# fancoil.net
KiCad netlist of a schematic drawn in EAGLE
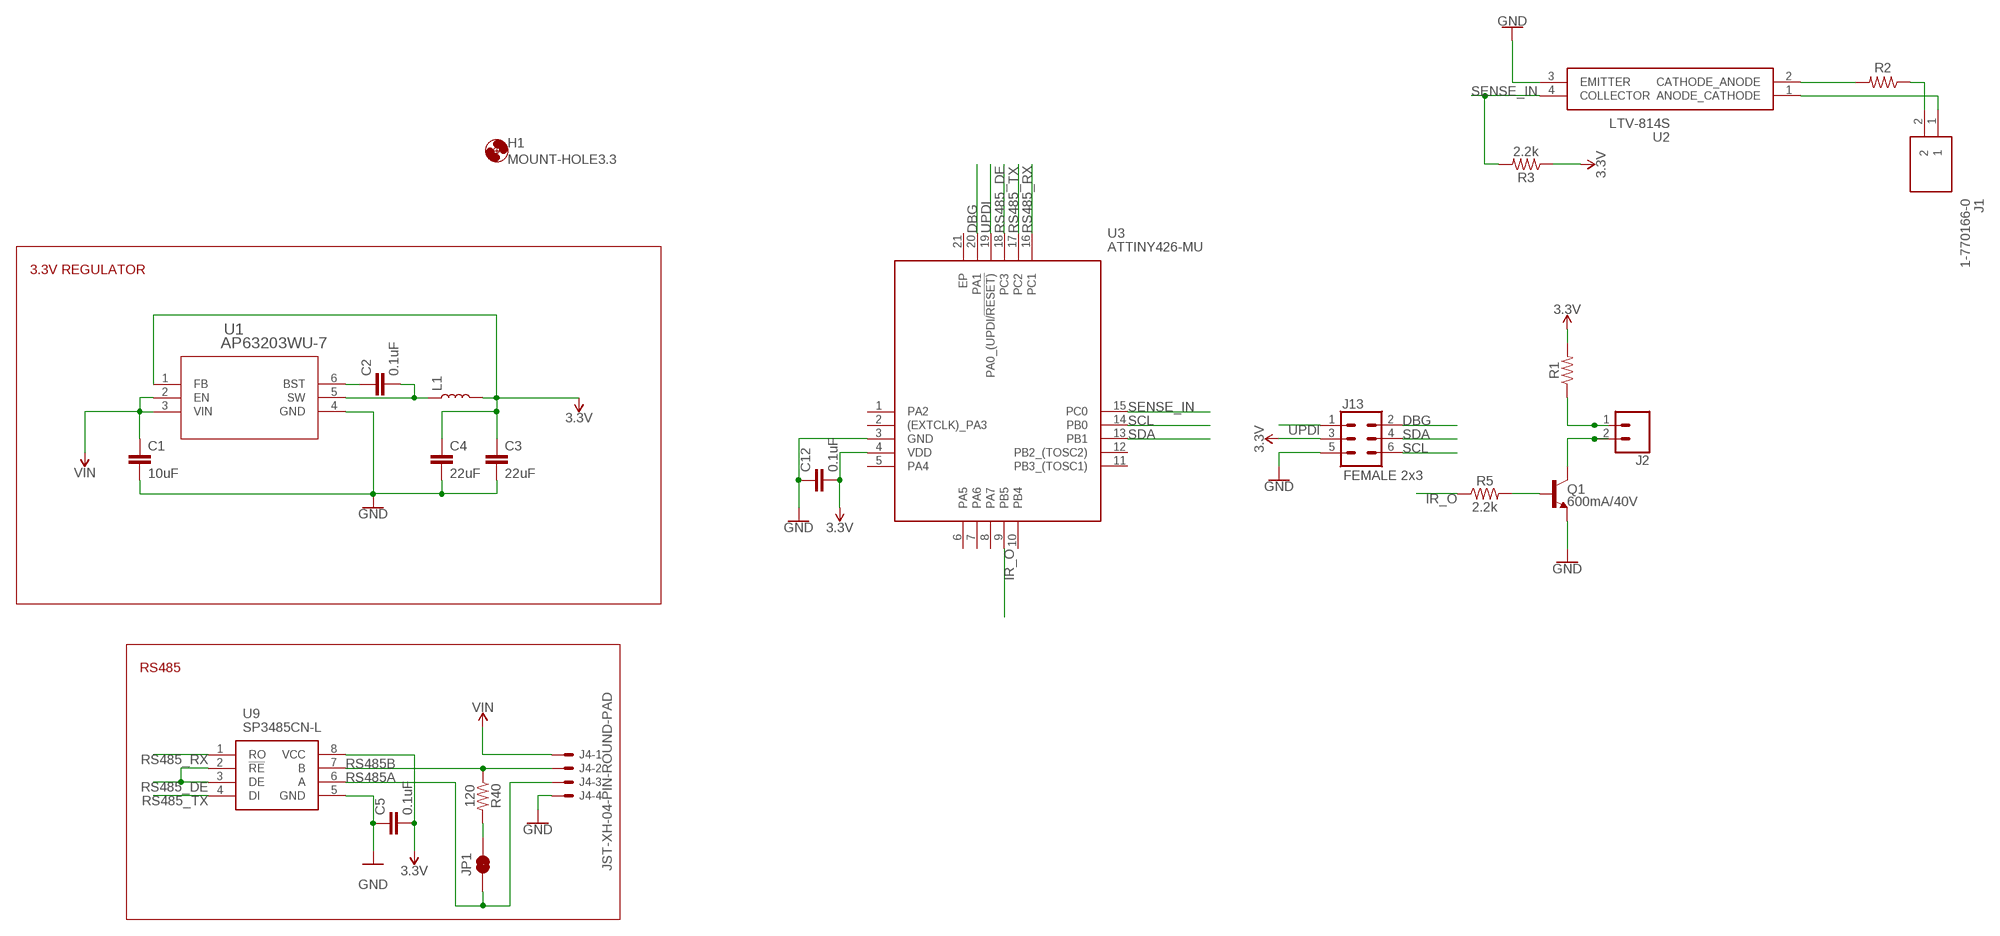
[diagram p0: schematic, sheet 1]

(export (version "E")
  (design (tool "Eeschema 10.0.6"))
  (components
    (comp (ref "C1")
      (value "10uF")
      (footprint "eagle-import:1206")
      (libsource (lib "eagle-import") (part "10UF-1206-6.3V-20%"))
    )
    (comp (ref "C2")
      (value "0.1uF")
      (footprint "eagle-import:0603")
      (libsource (lib "eagle-import") (part "0.1UF-0603-25V-5%"))
    )
    (comp (ref "C3")
      (value "22uF")
      (footprint "eagle-import:0805")
      (libsource (lib "eagle-import") (part "22UF-0805-6.3V-20%"))
    )
    (comp (ref "C4")
      (value "22uF")
      (footprint "eagle-import:0805")
      (libsource (lib "eagle-import") (part "22UF-0805-6.3V-20%"))
    )
    (comp (ref "C5")
      (value "0.1uF")
      (footprint "eagle-import:0603")
      (libsource (lib "eagle-import") (part "0.1UF-0603-25V-5%"))
    )
    (comp (ref "C12")
      (value "0.1uF")
      (footprint "eagle-import:0603")
      (libsource (lib "eagle-import") (part "0.1UF-0603-25V-5%"))
    )
    (comp (ref "H1")
      (value "MOUNT-HOLE3.3")
      (footprint "eagle-import:3,3")
      (libsource (lib "eagle-import") (part "MOUNT-HOLE3.3"))
    )
    (comp (ref "J1")
      (value "1-770166-0")
      (footprint "eagle-import:17701660")
      (fields (field (name "MOUSER_PART_NUMBER") "571-1-770166-0"))
      (libsource (lib "eagle-import") (part "1-770166-0"))
    )
    (comp (ref "J2")
      (value "CONN_02")
      (footprint "eagle-import:1X02")
      (libsource (lib "eagle-import") (part "CONN_02"))
    )
    (comp (ref "J4")
      (value "JST-XH-04-PIN-ROUND-PAD")
      (footprint "eagle-import:JST-XH-04-PACKAGE-ROUND-PAD")
      (libsource (lib "eagle-import") (part "JST-XH-04-PIN-ROUND-PAD"))
    )
    (comp (ref "J13")
      (value "FEMALE 2x3")
      (footprint "eagle-import:2X3")
      (libsource (lib "eagle-import") (part "CONN_03X2FEMALE"))
    )
    (comp (ref "JP1")
      (value "JUMPER-SMT_2_NC_TRACE_NO-SILK")
      (footprint "eagle-import:SMT-JUMPER_2_NC_TRACE_NO-SILK")
      (libsource (lib "eagle-import") (part "JUMPER-SMT_2_NC_TRACE_NO-SILK"))
    )
    (comp (ref "L1")
      (value "4.7μH_SHIELDED_INDUCTOR")
      (footprint "eagle-import:1008(2520)")
      (libsource (lib "eagle-import") (part "4.7μH_SHIELDED_INDUCTOR"))
    )
    (comp (ref "Q1")
      (value "600mA/40V")
      (footprint "eagle-import:SOT23-3")
      (libsource (lib "eagle-import") (part "TRANS_NPN-MMBT2222AL"))
    )
    (comp (ref "R1")
      (value "68OHM-0603-1/10W-1%")
      (footprint "eagle-import:0603")
      (libsource (lib "eagle-import") (part "68OHM-0603-1/10W-1%"))
    )
    (comp (ref "R2")
      (value "RESISTORAXIAL-0.3")
      (footprint "eagle-import:AXIAL-0.3")
      (libsource (lib "eagle-import") (part "RESISTORAXIAL-0.3"))
    )
    (comp (ref "R3")
      (value "2.2k")
      (footprint "eagle-import:0603")
      (libsource (lib "eagle-import") (part "2.2KOHM-0603-1/10W-1%"))
    )
    (comp (ref "R5")
      (value "2.2k")
      (footprint "eagle-import:0603")
      (libsource (lib "eagle-import") (part "2.2KOHM-0603-1/10W-1%"))
    )
    (comp (ref "R40")
      (value "120")
      (footprint "eagle-import:0603")
      (libsource (lib "eagle-import") (part "120OHM-0603-1/10W-5%"))
    )
    (comp (ref "U1")
      (value "AP63203WU-7")
      (footprint "eagle-import:SOIC_05WU-7_DIO")
      (fields (field (name "COPYRIGHT") "Copyright (C) 2023 Ultra Librarian. All rights reserved."))
      (libsource (lib "eagle-import") (part "AP63203WU-7"))
    )
    (comp (ref "U2")
      (value "LTV-814S")
      (footprint "eagle-import:SOP254P1016X460-4N")
      (fields (field (name "MOUSER_PART_NUMBER") "859-LTV-814S"))
      (libsource (lib "eagle-import") (part "LTV-814S"))
    )
    (comp (ref "U3")
      (value "ATTINY426-MU")
      (footprint "eagle-import:QFN40P300X300X90-21N")
      (fields (field (name "MOUSER_PART_NUMBER") "579-ATTINY426-MU"))
      (libsource (lib "eagle-import") (part "ATTINY426-MU"))
    )
    (comp (ref "U9")
      (value "SP3485CN-L")
      (footprint "eagle-import:SOIC127P600X175-8N")
      (fields (field (name "MOUSER_PART_NUMBER") "701-SP3485CN-L"))
      (libsource (lib "eagle-import") (part "SP3485CN-L"))
    )
  )
  (nets
    (net (code "1") (name "/DBG") (class "Default")
      (node (ref "J13") (pin "2") (pinfunction "2_2") (pintype "bidirectional"))
      (node (ref "U3") (pin "20") (pinfunction "PA1_20") (pintype "bidirectional"))
    )
    (net (code "2") (name "/IR_O") (class "Default")
      (node (ref "R5") (pin "1") (pinfunction "1_1") (pintype "passive"))
      (node (ref "U3") (pin "9") (pinfunction "PB5_9") (pintype "bidirectional"))
    )
    (net (code "3") (name "/RS485A") (class "Default")
      (node (ref "J4") (pin "3") (pinfunction "S_3") (pintype "passive"))
      (node (ref "JP1") (pin "1") (pinfunction "1_1") (pintype "passive"))
      (node (ref "U9") (pin "6") (pinfunction "A_6") (pintype "bidirectional"))
    )
    (net (code "4") (name "/RS485B") (class "Default")
      (node (ref "J4") (pin "2") (pinfunction "S_2") (pintype "passive"))
      (node (ref "R40") (pin "1") (pinfunction "1_1") (pintype "passive"))
      (node (ref "U9") (pin "7") (pinfunction "B_7") (pintype "bidirectional"))
    )
    (net (code "5") (name "/RS485_DE") (class "Default")
      (node (ref "U3") (pin "18") (pinfunction "PC3_18") (pintype "bidirectional"))
      (node (ref "U9") (pin "2") (pinfunction "~{RE}_2") (pintype "bidirectional"))
      (node (ref "U9") (pin "3") (pinfunction "DE_3") (pintype "bidirectional"))
    )
    (net (code "6") (name "/RS485_RX") (class "Default")
      (node (ref "U3") (pin "16") (pinfunction "PC1_16") (pintype "bidirectional"))
      (node (ref "U9") (pin "1") (pinfunction "RO_1") (pintype "bidirectional"))
    )
    (net (code "7") (name "/RS485_TX") (class "Default")
      (node (ref "U3") (pin "17") (pinfunction "PC2_17") (pintype "bidirectional"))
      (node (ref "U9") (pin "4") (pinfunction "DI_4") (pintype "bidirectional"))
    )
    (net (code "8") (name "/SCL") (class "Default")
      (node (ref "J13") (pin "6") (pinfunction "6_6") (pintype "bidirectional"))
      (node (ref "U3") (pin "14") (pinfunction "PB0_14") (pintype "bidirectional"))
    )
    (net (code "9") (name "/SDA") (class "Default")
      (node (ref "J13") (pin "4") (pinfunction "4_4") (pintype "bidirectional"))
      (node (ref "U3") (pin "13") (pinfunction "PB1_13") (pintype "bidirectional"))
    )
    (net (code "10") (name "/SENSE_IN") (class "Default")
      (node (ref "R3") (pin "2") (pinfunction "2_2") (pintype "passive"))
      (node (ref "U2") (pin "4") (pinfunction "COLLECTOR_4") (pintype "output"))
      (node (ref "U3") (pin "15") (pinfunction "PC0_15") (pintype "bidirectional"))
    )
    (net (code "11") (name "/UPDI") (class "Default")
      (node (ref "J13") (pin "1") (pinfunction "1_1") (pintype "bidirectional"))
      (node (ref "U3") (pin "19") (pinfunction "PA0_(UPDI/~{RESET})_19") (pintype "bidirectional"))
    )
    (net (code "12") (name "3.3V") (class "Default")
      (node (ref "C12") (pin "2") (pinfunction "2_2") (pintype "passive"))
      (node (ref "C3") (pin "1") (pinfunction "1_1") (pintype "passive"))
      (node (ref "C4") (pin "1") (pinfunction "1_1") (pintype "passive"))
      (node (ref "C5") (pin "2") (pinfunction "2_2") (pintype "passive"))
      (node (ref "J13") (pin "3") (pinfunction "3_3") (pintype "bidirectional"))
      (node (ref "L1") (pin "2") (pinfunction "2_2") (pintype "passive"))
      (node (ref "R1") (pin "2") (pinfunction "2_2") (pintype "passive"))
      (node (ref "R3") (pin "1") (pinfunction "1_1") (pintype "passive"))
      (node (ref "U1") (pin "1") (pinfunction "FB_1") (pintype "passive"))
      (node (ref "U3") (pin "4") (pinfunction "VDD_4") (pintype "bidirectional"))
      (node (ref "U9") (pin "8") (pinfunction "VCC_8") (pintype "bidirectional"))
    )
    (net (code "13") (name "GND") (class "Default")
      (node (ref "C1") (pin "2") (pinfunction "2_2") (pintype "passive"))
      (node (ref "C12") (pin "1") (pinfunction "1_1") (pintype "passive"))
      (node (ref "C3") (pin "2") (pinfunction "2_2") (pintype "passive"))
      (node (ref "C4") (pin "2") (pinfunction "2_2") (pintype "passive"))
      (node (ref "C5") (pin "1") (pinfunction "1_1") (pintype "passive"))
      (node (ref "J13") (pin "5") (pinfunction "5_5") (pintype "bidirectional"))
      (node (ref "J4") (pin "4") (pinfunction "S_4") (pintype "passive"))
      (node (ref "Q1") (pin "2") (pinfunction "E_2") (pintype "passive"))
      (node (ref "U1") (pin "4") (pinfunction "GND_4") (pintype "passive"))
      (node (ref "U2") (pin "3") (pinfunction "EMITTER_3") (pintype "output"))
      (node (ref "U3") (pin "3") (pinfunction "GND_3") (pintype "bidirectional"))
      (node (ref "U9") (pin "5") (pinfunction "GND_5") (pintype "bidirectional"))
    )
    (net (code "14") (name "Net-(J2-Pad1)") (class "Default")
      (node (ref "J2") (pin "1") (pinfunction "1_1") (pintype "passive"))
      (node (ref "R1") (pin "1") (pinfunction "1_1") (pintype "passive"))
    )
    (net (code "15") (name "Net-(JP1-Pad2)") (class "Default")
      (node (ref "JP1") (pin "2") (pinfunction "2_2") (pintype "passive"))
      (node (ref "R40") (pin "2") (pinfunction "2_2") (pintype "passive"))
    )
    (net (code "16") (name "Net-(Q1-B)") (class "Default")
      (node (ref "Q1") (pin "1") (pinfunction "B_1") (pintype "passive"))
      (node (ref "R5") (pin "2") (pinfunction "2_2") (pintype "passive"))
    )
    (net (code "17") (name "Net-(Q1-C)") (class "Default")
      (node (ref "J2") (pin "2") (pinfunction "2_2") (pintype "passive"))
      (node (ref "Q1") (pin "3") (pinfunction "C_3") (pintype "passive"))
    )
    (net (code "18") (name "Net-(R2-1)") (class "Default")
      (node (ref "J1") (pin "2") (pinfunction "2_2") (pintype "bidirectional"))
      (node (ref "R2") (pin "P$1") (pinfunction "1_P$1") (pintype "passive"))
    )
    (net (code "19") (name "Net-(R2-2)") (class "Default")
      (node (ref "R2") (pin "P$2") (pinfunction "2_P$2") (pintype "passive"))
      (node (ref "U2") (pin "2") (pinfunction "CATHODE_ANODE_2") (pintype "input"))
    )
    (net (code "20") (name "Net-(U1-BST)") (class "Default")
      (node (ref "C2") (pin "1") (pinfunction "1_1") (pintype "passive"))
      (node (ref "U1") (pin "6") (pinfunction "BST_6") (pintype "passive"))
    )
    (net (code "21") (name "Net-(U1-SW)") (class "Default")
      (node (ref "C2") (pin "2") (pinfunction "2_2") (pintype "passive"))
      (node (ref "L1") (pin "1") (pinfunction "1_1") (pintype "passive"))
      (node (ref "U1") (pin "5") (pinfunction "SW_5") (pintype "passive"))
    )
    (net (code "22") (name "Net-(U2-ANODE_CATHODE)") (class "Default")
      (node (ref "J1") (pin "1") (pinfunction "1_1") (pintype "bidirectional"))
      (node (ref "U2") (pin "1") (pinfunction "ANODE_CATHODE_1") (pintype "input"))
    )
    (net (code "23") (name "VIN") (class "Default")
      (node (ref "C1") (pin "1") (pinfunction "1_1") (pintype "passive"))
      (node (ref "J4") (pin "1") (pinfunction "S_1") (pintype "passive"))
      (node (ref "U1") (pin "2") (pinfunction "EN_2") (pintype "passive"))
      (node (ref "U1") (pin "3") (pinfunction "VIN_3") (pintype "passive"))
    )
    (net (code "24") (name "unconnected-(U3-(EXTCLK)_PA3-Pad2)") (class "Default")
      (node (ref "U3") (pin "2") (pinfunction "(EXTCLK)_PA3_2") (pintype "bidirectional"))
    )
    (net (code "25") (name "unconnected-(U3-EP-Pad21)") (class "Default")
      (node (ref "U3") (pin "21") (pinfunction "EP_21") (pintype "bidirectional"))
    )
    (net (code "26") (name "unconnected-(U3-PA2-Pad1)") (class "Default")
      (node (ref "U3") (pin "1") (pinfunction "PA2_1") (pintype "bidirectional"))
    )
    (net (code "27") (name "unconnected-(U3-PA4-Pad5)") (class "Default")
      (node (ref "U3") (pin "5") (pinfunction "PA4_5") (pintype "bidirectional"))
    )
    (net (code "28") (name "unconnected-(U3-PA5-Pad6)") (class "Default")
      (node (ref "U3") (pin "6") (pinfunction "PA5_6") (pintype "bidirectional"))
    )
    (net (code "29") (name "unconnected-(U3-PA6-Pad7)") (class "Default")
      (node (ref "U3") (pin "7") (pinfunction "PA6_7") (pintype "bidirectional"))
    )
    (net (code "30") (name "unconnected-(U3-PA7-Pad8)") (class "Default")
      (node (ref "U3") (pin "8") (pinfunction "PA7_8") (pintype "bidirectional"))
    )
    (net (code "31") (name "unconnected-(U3-PB2_(TOSC2)-Pad12)") (class "Default")
      (node (ref "U3") (pin "12") (pinfunction "PB2_(TOSC2)_12") (pintype "bidirectional"))
    )
    (net (code "32") (name "unconnected-(U3-PB3_(TOSC1)-Pad11)") (class "Default")
      (node (ref "U3") (pin "11") (pinfunction "PB3_(TOSC1)_11") (pintype "bidirectional"))
    )
    (net (code "33") (name "unconnected-(U3-PB4-Pad10)") (class "Default")
      (node (ref "U3") (pin "10") (pinfunction "PB4_10") (pintype "bidirectional"))
    )
  )
)
